# esquema_vortex_001.net
KiCad netlist of a schematic drawn in EAGLE
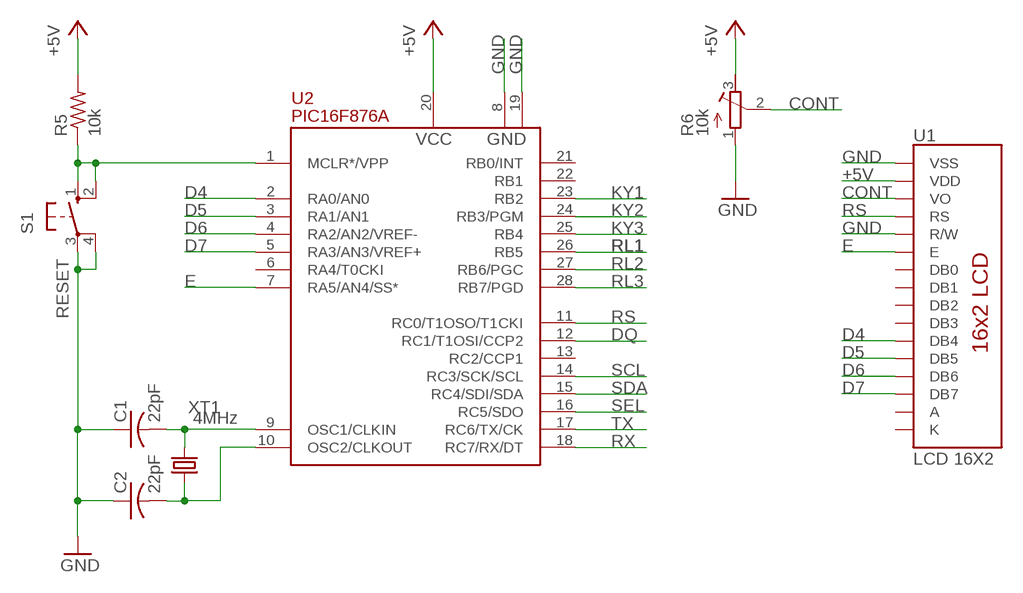
[diagram p0: schematic, sheet 1]
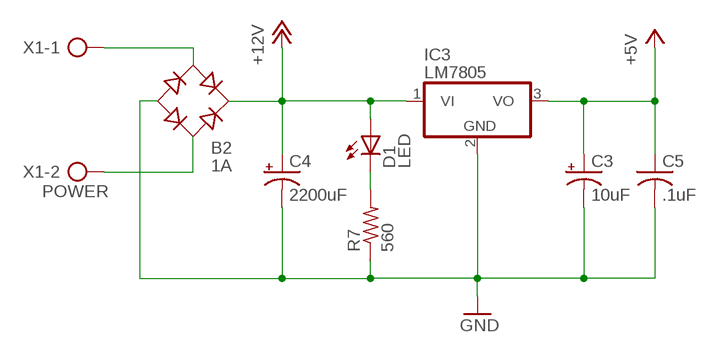
[diagram p1: schematic, sheet 2]
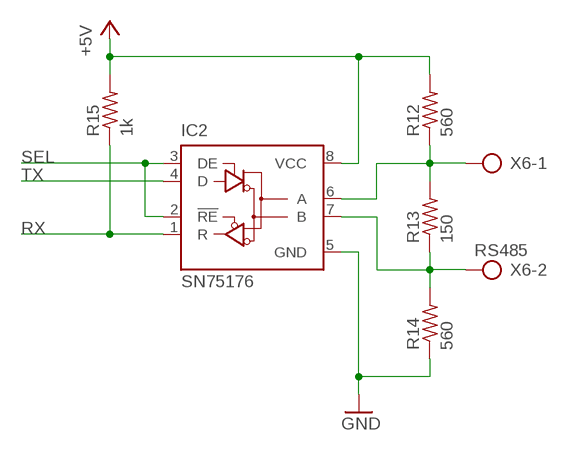
[diagram p2: schematic, sheet 3]
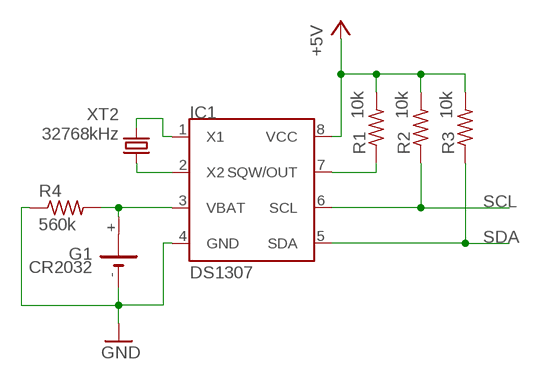
[diagram p3: schematic, sheet 4]
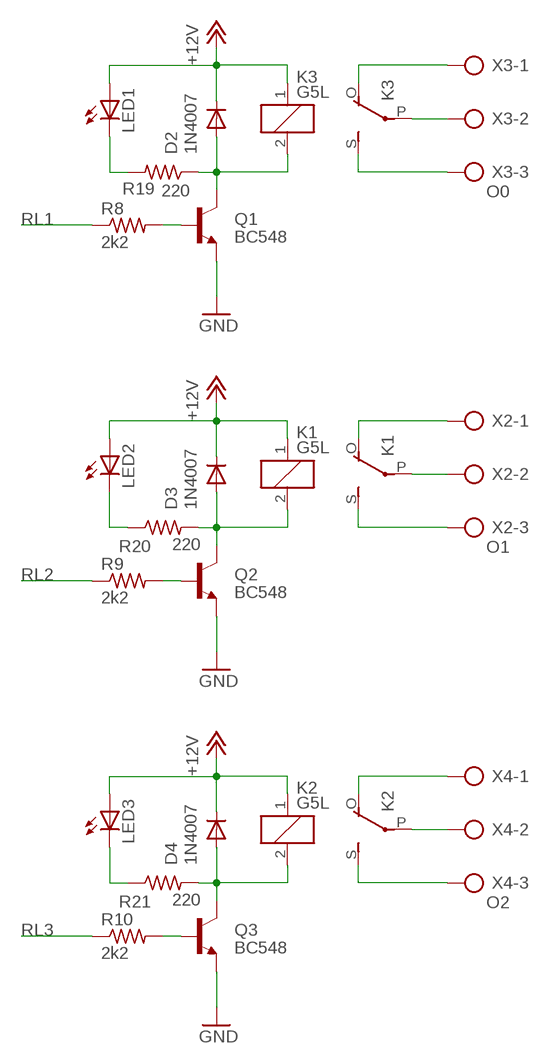
[diagram p4: schematic, sheet 5]
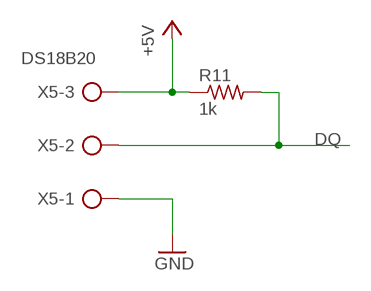
[diagram p5: schematic, sheet 6]
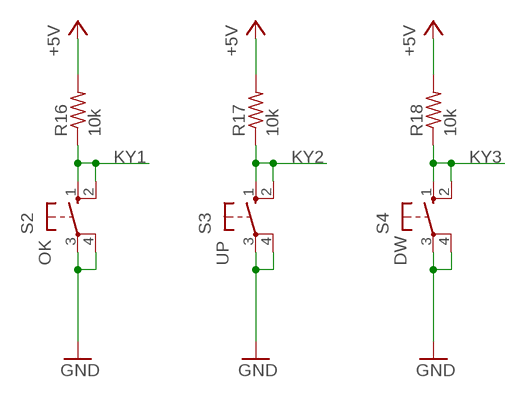
[diagram p6: schematic, sheet 7]

(export (version "E")
  (design (tool "Eeschema 10.0.6"))
  (components
    (comp (ref "IC2")
      (value "SN75176")
      (footprint "eagle-import:DIL08")
      (libsource (lib "eagle-import") (part "75176AP"))
    )
    (comp (ref "R12")
      (value "560")
      (footprint "eagle-import:0204_7")
      (libsource (lib "eagle-import") (part "R-US_0204/7"))
    )
    (comp (ref "R13")
      (value "150")
      (footprint "eagle-import:0204_7")
      (libsource (lib "eagle-import") (part "R-US_0204/7"))
    )
    (comp (ref "R14")
      (value "560")
      (footprint "eagle-import:0204_7")
      (libsource (lib "eagle-import") (part "R-US_0204/7"))
    )
    (comp (ref "R15")
      (value "1k")
      (footprint "eagle-import:0204_7")
      (libsource (lib "eagle-import") (part "R-US_0204/7"))
    )
    (comp (ref "X6")
      (value "RS485")
      (footprint "eagle-import:AK500_2-H")
      (libsource (lib "eagle-import") (part "AK500/2-H"))
    )
    (comp (ref "C1")
      (value "22pF")
      (footprint "eagle-import:C025-030X050")
      (libsource (lib "eagle-import") (part "C-US025-030X050"))
    )
    (comp (ref "C2")
      (value "22pF")
      (footprint "eagle-import:C025-030X050")
      (libsource (lib "eagle-import") (part "C-US025-030X050"))
    )
    (comp (ref "R5")
      (value "10k")
      (footprint "eagle-import:0204_7")
      (libsource (lib "eagle-import") (part "rcl_R-US_0204/7"))
    )
    (comp (ref "R6")
      (value "10k")
      (footprint "eagle-import:RTRIM3296W")
      (libsource (lib "eagle-import") (part "R-TRIMM3296W"))
    )
    (comp (ref "S1")
      (value "RESET")
      (footprint "eagle-import:B3F-10XX")
      (fields (field (name "MPN") "B3F-1000"))
      (libsource (lib "eagle-import") (part "10-XX"))
    )
    (comp (ref "U1")
      (value "LCD 16X2")
      (footprint "eagle-import:LCD-16X2")
      (libsource (lib "eagle-import") (part "LCD-16X2SILK"))
    )
    (comp (ref "U2")
      (value "PIC16F876A")
      (footprint "eagle-import:DIL28-3")
      (libsource (lib "eagle-import") (part "16F876SP"))
    )
    (comp (ref "XT1")
      (value "4MHz")
      (footprint "eagle-import:HC49_S")
      (libsource (lib "eagle-import") (part "CRYSTALHC49S"))
    )
    (comp (ref "D2")
      (value "1N4007")
      (footprint "eagle-import:DO41-10")
      (libsource (lib "eagle-import") (part "1N4004"))
    )
    (comp (ref "D3")
      (value "1N4007")
      (footprint "eagle-import:DO41-10")
      (libsource (lib "eagle-import") (part "1N4004"))
    )
    (comp (ref "D4")
      (value "1N4007")
      (footprint "eagle-import:DO41-10")
      (libsource (lib "eagle-import") (part "1N4004"))
    )
    (comp (ref "K1")
      (value "G5L")
      (footprint "eagle-import:G5LE")
      (libsource (lib "eagle-import") (part "G5L"))
    )
    (comp (ref "K2")
      (value "G5L")
      (footprint "eagle-import:G5LE")
      (libsource (lib "eagle-import") (part "G5L"))
    )
    (comp (ref "K3")
      (value "G5L")
      (footprint "eagle-import:G5LE")
      (libsource (lib "eagle-import") (part "G5L"))
    )
    (comp (ref "LED1")
      (value "LED")
      (footprint "eagle-import:LED3MM")
      (libsource (lib "eagle-import") (part "led_LED3MM"))
    )
    (comp (ref "LED2")
      (value "LED")
      (footprint "eagle-import:LED3MM")
      (libsource (lib "eagle-import") (part "led_LED3MM"))
    )
    (comp (ref "LED3")
      (value "LED")
      (footprint "eagle-import:LED3MM")
      (libsource (lib "eagle-import") (part "led_LED3MM"))
    )
    (comp (ref "Q1")
      (value "BC548")
      (footprint "eagle-import:TO92-EBC")
      (libsource (lib "eagle-import") (part "BC548"))
    )
    (comp (ref "Q2")
      (value "BC548")
      (footprint "eagle-import:TO92-EBC")
      (libsource (lib "eagle-import") (part "BC548"))
    )
    (comp (ref "Q3")
      (value "BC548")
      (footprint "eagle-import:TO92-EBC")
      (libsource (lib "eagle-import") (part "BC548"))
    )
    (comp (ref "R8")
      (value "2k2")
      (footprint "eagle-import:0204_7")
      (libsource (lib "eagle-import") (part "R-US_0204/7"))
    )
    (comp (ref "R9")
      (value "2k2")
      (footprint "eagle-import:0204_7")
      (libsource (lib "eagle-import") (part "R-US_0204/7"))
    )
    (comp (ref "R10")
      (value "2k2")
      (footprint "eagle-import:0204_7")
      (libsource (lib "eagle-import") (part "R-US_0204/7"))
    )
    (comp (ref "R19")
      (value "220")
      (footprint "eagle-import:0204_7")
      (libsource (lib "eagle-import") (part "R-US_0204/7"))
    )
    (comp (ref "R20")
      (value "220")
      (footprint "eagle-import:0204_7")
      (libsource (lib "eagle-import") (part "R-US_0204/7"))
    )
    (comp (ref "R21")
      (value "220")
      (footprint "eagle-import:0204_7")
      (libsource (lib "eagle-import") (part "R-US_0204/7"))
    )
    (comp (ref "X2")
      (value "O1")
      (footprint "eagle-import:AK500_3")
      (libsource (lib "eagle-import") (part "AK500/3"))
    )
    (comp (ref "X3")
      (value "O0")
      (footprint "eagle-import:AK500_3")
      (libsource (lib "eagle-import") (part "AK500/3"))
    )
    (comp (ref "X4")
      (value "O2")
      (footprint "eagle-import:AK500_3")
      (libsource (lib "eagle-import") (part "AK500/3"))
    )
    (comp (ref "G1")
      (value "CR2032")
      (footprint "eagle-import:CR2032H")
      (libsource (lib "eagle-import") (part "CR2032H"))
    )
    (comp (ref "IC1")
      (value "DS1307")
      (footprint "eagle-import:DIL08")
      (libsource (lib "eagle-import") (part "DS1307PDIP"))
    )
    (comp (ref "R1")
      (value "10k")
      (footprint "eagle-import:0204_7")
      (libsource (lib "eagle-import") (part "R-US_0204/7"))
    )
    (comp (ref "R2")
      (value "10k")
      (footprint "eagle-import:0204_7")
      (libsource (lib "eagle-import") (part "R-US_0204/7"))
    )
    (comp (ref "R3")
      (value "10k")
      (footprint "eagle-import:0204_7")
      (libsource (lib "eagle-import") (part "R-US_0204/7"))
    )
    (comp (ref "R4")
      (value "560k")
      (footprint "eagle-import:0204_7")
      (libsource (lib "eagle-import") (part "R-US_0204/7"))
    )
    (comp (ref "XT2")
      (value "32768kHz")
      (footprint "eagle-import:HC49_S")
      (libsource (lib "eagle-import") (part "CRYSTALHC49S"))
    )
    (comp (ref "B2")
      (value "1A")
      (footprint "eagle-import:RB1A")
      (libsource (lib "eagle-import") (part "RB1A"))
    )
    (comp (ref "C3")
      (value "10uF")
      (footprint "eagle-import:E2,5-7")
      (libsource (lib "eagle-import") (part "CPOL-USE2.5-7"))
    )
    (comp (ref "C4")
      (value "2200uF")
      (footprint "eagle-import:E3,5-10")
      (libsource (lib "eagle-import") (part "CPOL-USE3.5-10"))
    )
    (comp (ref "C5")
      (value ".1uF")
      (footprint "eagle-import:C050-024X044")
      (libsource (lib "eagle-import") (part "C-US050-024X044"))
    )
    (comp (ref "D1")
      (value "LED")
      (footprint "eagle-import:LED3MM")
      (libsource (lib "eagle-import") (part "LED3MM"))
    )
    (comp (ref "IC3")
      (value "LM7805")
      (footprint "eagle-import:TO220V")
      (libsource (lib "eagle-import") (part "78TV12"))
    )
    (comp (ref "R7")
      (value "560")
      (footprint "eagle-import:0204_7")
      (libsource (lib "eagle-import") (part "rcl_R-US_0204/7"))
    )
    (comp (ref "X1")
      (value "POWER")
      (footprint "eagle-import:AK500_2")
      (libsource (lib "eagle-import") (part "AK500/2"))
    )
    (comp (ref "R11")
      (value "1k")
      (footprint "eagle-import:0204_7")
      (libsource (lib "eagle-import") (part "R-US_0204/7"))
    )
    (comp (ref "X5")
      (value "DS18B20")
      (footprint "eagle-import:AK500_3-H")
      (libsource (lib "eagle-import") (part "AK500/3-H"))
    )
    (comp (ref "R16")
      (value "10k")
      (footprint "eagle-import:0204_7")
      (libsource (lib "eagle-import") (part "rcl_R-US_0204/7"))
    )
    (comp (ref "R17")
      (value "10k")
      (footprint "eagle-import:0204_7")
      (libsource (lib "eagle-import") (part "rcl_R-US_0204/7"))
    )
    (comp (ref "R18")
      (value "10k")
      (footprint "eagle-import:0204_7")
      (libsource (lib "eagle-import") (part "rcl_R-US_0204/7"))
    )
    (comp (ref "S2")
      (value "OK")
      (footprint "eagle-import:B3F-10XX")
      (fields (field (name "MPN") "B3F-1000"))
      (libsource (lib "eagle-import") (part "10-XX"))
    )
    (comp (ref "S3")
      (value "UP")
      (footprint "eagle-import:B3F-10XX")
      (fields (field (name "MPN") "B3F-1000"))
      (libsource (lib "eagle-import") (part "10-XX"))
    )
    (comp (ref "S4")
      (value "DW")
      (footprint "eagle-import:B3F-10XX")
      (fields (field (name "MPN") "B3F-1000"))
      (libsource (lib "eagle-import") (part "10-XX"))
    )
  )
  (nets
    (net (code "1") (name "+5V") (class "Default")
      (node (ref "C3") (pin "+") (pinfunction "+_+") (pintype "passive"))
      (node (ref "C5") (pin "1") (pinfunction "1_1") (pintype "passive"))
      (node (ref "IC1") (pin "8") (pinfunction "VCC_8") (pintype "power_in"))
      (node (ref "IC2") (pin "8") (pinfunction "VCC_8") (pintype "power_in"))
      (node (ref "IC3") (pin "3") (pinfunction "VO_3") (pintype "passive"))
      (node (ref "R1") (pin "2") (pinfunction "2_2") (pintype "passive"))
      (node (ref "R11") (pin "1") (pinfunction "1_1") (pintype "passive"))
      (node (ref "R12") (pin "2") (pinfunction "2_2") (pintype "passive"))
      (node (ref "R15") (pin "2") (pinfunction "2_2") (pintype "passive"))
      (node (ref "R16") (pin "2") (pinfunction "2_2") (pintype "passive"))
      (node (ref "R17") (pin "2") (pinfunction "2_2") (pintype "passive"))
      (node (ref "R18") (pin "2") (pinfunction "2_2") (pintype "passive"))
      (node (ref "R2") (pin "2") (pinfunction "2_2") (pintype "passive"))
      (node (ref "R3") (pin "2") (pinfunction "2_2") (pintype "passive"))
      (node (ref "R5") (pin "2") (pinfunction "2_2") (pintype "passive"))
      (node (ref "R6") (pin "3") (pinfunction "E_3") (pintype "passive"))
      (node (ref "U1") (pin "2") (pinfunction "VDD_2") (pintype "power_in"))
      (node (ref "U2") (pin "20") (pinfunction "VCC_20") (pintype "power_in"))
      (node (ref "X5") (pin "3") (pinfunction "KL_3") (pintype "passive"))
    )
    (net (code "2") (name "+12V") (class "Default")
      (node (ref "B2") (pin "+") (pinfunction "+_+") (pintype "passive"))
      (node (ref "C4") (pin "+") (pinfunction "+_+") (pintype "passive"))
      (node (ref "D1") (pin "A") (pinfunction "A_A") (pintype "passive"))
      (node (ref "D2") (pin "C") (pinfunction "C_C") (pintype "passive"))
      (node (ref "D3") (pin "C") (pinfunction "C_C") (pintype "passive"))
      (node (ref "D4") (pin "C") (pinfunction "C_C") (pintype "passive"))
      (node (ref "IC3") (pin "1") (pinfunction "VI_1") (pintype "input"))
      (node (ref "K1") (pin "1") (pinfunction "1_1") (pintype "passive"))
      (node (ref "K2") (pin "1") (pinfunction "1_1") (pintype "passive"))
      (node (ref "K3") (pin "1") (pinfunction "1_1") (pintype "passive"))
      (node (ref "LED1") (pin "A") (pinfunction "A_A") (pintype "passive"))
      (node (ref "LED2") (pin "A") (pinfunction "A_A") (pintype "passive"))
      (node (ref "LED3") (pin "A") (pinfunction "A_A") (pintype "passive"))
    )
    (net (code "3") (name "A") (class "Default")
      (node (ref "U1") (pin "15") (pinfunction "A_15") (pintype "power_in"))
    )
    (net (code "4") (name "CONT") (class "Default")
      (node (ref "R6") (pin "2") (pinfunction "S_2") (pintype "passive"))
      (node (ref "U1") (pin "3") (pinfunction "VO_3") (pintype "bidirectional"))
    )
    (net (code "5") (name "D4") (class "Default")
      (node (ref "U1") (pin "11") (pinfunction "DB4_11") (pintype "bidirectional"))
      (node (ref "U2") (pin "2") (pinfunction "RA0/AN0_2") (pintype "bidirectional"))
    )
    (net (code "6") (name "D5") (class "Default")
      (node (ref "U1") (pin "12") (pinfunction "DB5_12") (pintype "bidirectional"))
      (node (ref "U2") (pin "3") (pinfunction "RA1/AN1_3") (pintype "bidirectional"))
    )
    (net (code "7") (name "D6") (class "Default")
      (node (ref "U1") (pin "13") (pinfunction "DB6_13") (pintype "bidirectional"))
      (node (ref "U2") (pin "4") (pinfunction "RA2/AN2/VREF-_4") (pintype "bidirectional"))
    )
    (net (code "8") (name "D7") (class "Default")
      (node (ref "U1") (pin "14") (pinfunction "DB7_14") (pintype "bidirectional"))
      (node (ref "U2") (pin "5") (pinfunction "RA3/AN3/VREF+_5") (pintype "bidirectional"))
    )
    (net (code "9") (name "DQ") (class "Default")
      (node (ref "R11") (pin "2") (pinfunction "2_2") (pintype "passive"))
      (node (ref "U2") (pin "12") (pinfunction "RC1/T1OSI/CCP2_12") (pintype "bidirectional"))
      (node (ref "X5") (pin "2") (pinfunction "KL_2") (pintype "passive"))
    )
    (net (code "10") (name "E") (class "Default")
      (node (ref "U1") (pin "6") (pinfunction "E_6") (pintype "input"))
      (node (ref "U2") (pin "7") (pinfunction "RA5/AN4/SS*_7") (pintype "bidirectional"))
    )
    (net (code "11") (name "GND") (class "Default")
      (node (ref "B2") (pin "-") (pinfunction "-_-") (pintype "passive"))
      (node (ref "C1") (pin "1") (pinfunction "1_1") (pintype "passive"))
      (node (ref "C2") (pin "1") (pinfunction "1_1") (pintype "passive"))
      (node (ref "C3") (pin "-") (pinfunction "-_-") (pintype "passive"))
      (node (ref "C4") (pin "-") (pinfunction "-_-") (pintype "passive"))
      (node (ref "C5") (pin "2") (pinfunction "2_2") (pintype "passive"))
      (node (ref "G1") (pin "-") (pinfunction "-_-") (pintype "passive"))
      (node (ref "IC1") (pin "4") (pinfunction "GND_4") (pintype "power_in"))
      (node (ref "IC2") (pin "5") (pinfunction "GND_5") (pintype "power_in"))
      (node (ref "IC3") (pin "2") (pinfunction "GND_2") (pintype "passive"))
      (node (ref "Q1") (pin "E") (pinfunction "E_E") (pintype "passive"))
      (node (ref "Q2") (pin "E") (pinfunction "E_E") (pintype "passive"))
      (node (ref "Q3") (pin "E") (pinfunction "E_E") (pintype "passive"))
      (node (ref "R14") (pin "1") (pinfunction "1_1") (pintype "passive"))
      (node (ref "R4") (pin "1") (pinfunction "1_1") (pintype "passive"))
      (node (ref "R6") (pin "1") (pinfunction "A_1") (pintype "passive"))
      (node (ref "R7") (pin "1") (pinfunction "1_1") (pintype "passive"))
      (node (ref "S1") (pin "3") (pinfunction "P_3") (pintype "passive"))
      (node (ref "S1") (pin "4") (pinfunction "P1_4") (pintype "passive"))
      (node (ref "S2") (pin "3") (pinfunction "P_3") (pintype "passive"))
      (node (ref "S2") (pin "4") (pinfunction "P1_4") (pintype "passive"))
      (node (ref "S3") (pin "3") (pinfunction "P_3") (pintype "passive"))
      (node (ref "S3") (pin "4") (pinfunction "P1_4") (pintype "passive"))
      (node (ref "S4") (pin "3") (pinfunction "P_3") (pintype "passive"))
      (node (ref "S4") (pin "4") (pinfunction "P1_4") (pintype "passive"))
      (node (ref "U1") (pin "1") (pinfunction "VSS_1") (pintype "power_in"))
      (node (ref "U1") (pin "5") (pinfunction "R/W_5") (pintype "input"))
      (node (ref "U2") (pin "19") (pinfunction "GND_19") (pintype "power_in"))
      (node (ref "U2") (pin "8") (pinfunction "GND_8") (pintype "power_in"))
      (node (ref "X5") (pin "1") (pinfunction "KL_1") (pintype "passive"))
    )
    (net (code "12") (name "K") (class "Default")
      (node (ref "U1") (pin "16") (pinfunction "K_16") (pintype "power_in"))
    )
    (net (code "13") (name "KY1") (class "Default")
      (node (ref "R16") (pin "1") (pinfunction "1_1") (pintype "passive"))
      (node (ref "S2") (pin "1") (pinfunction "S_1") (pintype "passive"))
      (node (ref "S2") (pin "2") (pinfunction "S1_2") (pintype "passive"))
      (node (ref "U2") (pin "23") (pinfunction "RB2_23") (pintype "bidirectional"))
    )
    (net (code "14") (name "KY2") (class "Default")
      (node (ref "R17") (pin "1") (pinfunction "1_1") (pintype "passive"))
      (node (ref "S3") (pin "1") (pinfunction "S_1") (pintype "passive"))
      (node (ref "S3") (pin "2") (pinfunction "S1_2") (pintype "passive"))
      (node (ref "U2") (pin "24") (pinfunction "RB3/PGM_24") (pintype "bidirectional"))
    )
    (net (code "15") (name "KY3") (class "Default")
      (node (ref "R18") (pin "1") (pinfunction "1_1") (pintype "passive"))
      (node (ref "S4") (pin "1") (pinfunction "S_1") (pintype "passive"))
      (node (ref "S4") (pin "2") (pinfunction "S1_2") (pintype "passive"))
      (node (ref "U2") (pin "25") (pinfunction "RB4_25") (pintype "bidirectional"))
    )
    (net (code "16") (name "Net-(D1-C)") (class "Default")
      (node (ref "D1") (pin "K") (pinfunction "C_K") (pintype "passive"))
      (node (ref "R7") (pin "2") (pinfunction "2_2") (pintype "passive"))
    )
    (net (code "17") (name "Net-(D2-PadA)") (class "Default")
      (node (ref "D2") (pin "A") (pinfunction "A_A") (pintype "passive"))
      (node (ref "K3") (pin "2") (pinfunction "2_2") (pintype "passive"))
      (node (ref "Q1") (pin "C") (pinfunction "C_C") (pintype "passive"))
      (node (ref "R19") (pin "1") (pinfunction "1_1") (pintype "passive"))
    )
    (net (code "18") (name "Net-(D3-PadA)") (class "Default")
      (node (ref "D3") (pin "A") (pinfunction "A_A") (pintype "passive"))
      (node (ref "K1") (pin "2") (pinfunction "2_2") (pintype "passive"))
      (node (ref "Q2") (pin "C") (pinfunction "C_C") (pintype "passive"))
      (node (ref "R20") (pin "2") (pinfunction "2_2") (pintype "passive"))
    )
    (net (code "19") (name "Net-(D4-PadA)") (class "Default")
      (node (ref "D4") (pin "A") (pinfunction "A_A") (pintype "passive"))
      (node (ref "K2") (pin "2") (pinfunction "2_2") (pintype "passive"))
      (node (ref "Q3") (pin "C") (pinfunction "C_C") (pintype "passive"))
      (node (ref "R21") (pin "2") (pinfunction "2_2") (pintype "passive"))
    )
    (net (code "20") (name "Net-(IC1-SQW{slash}OUT)") (class "Default")
      (node (ref "IC1") (pin "7") (pinfunction "SQW/OUT_7") (pintype "output"))
      (node (ref "R1") (pin "1") (pinfunction "1_1") (pintype "passive"))
    )
    (net (code "21") (name "Net-(IC1-VBAT)") (class "Default")
      (node (ref "G1") (pin "+") (pinfunction "+_+") (pintype "passive"))
      (node (ref "IC1") (pin "3") (pinfunction "VBAT_3") (pintype "power_in"))
      (node (ref "R4") (pin "2") (pinfunction "2_2") (pintype "passive"))
    )
    (net (code "22") (name "Net-(IC1-X1)") (class "Default")
      (node (ref "IC1") (pin "1") (pinfunction "X1_1") (pintype "input"))
      (node (ref "XT2") (pin "2") (pinfunction "2_2") (pintype "passive"))
    )
    (net (code "23") (name "Net-(IC1-X2)") (class "Default")
      (node (ref "IC1") (pin "2") (pinfunction "X2_2") (pintype "output"))
      (node (ref "XT2") (pin "1") (pinfunction "1_1") (pintype "passive"))
    )
    (net (code "24") (name "Net-(IC2-A)") (class "Default")
      (node (ref "IC2") (pin "6") (pinfunction "A_6") (pintype "output"))
      (node (ref "R12") (pin "1") (pinfunction "1_1") (pintype "passive"))
      (node (ref "R13") (pin "2") (pinfunction "2_2") (pintype "passive"))
      (node (ref "X6") (pin "1") (pinfunction "KL_1") (pintype "passive"))
    )
    (net (code "25") (name "Net-(IC2-B)") (class "Default")
      (node (ref "IC2") (pin "7") (pinfunction "B_7") (pintype "output"))
      (node (ref "R13") (pin "1") (pinfunction "1_1") (pintype "passive"))
      (node (ref "R14") (pin "2") (pinfunction "2_2") (pintype "passive"))
      (node (ref "X6") (pin "2") (pinfunction "KL_2") (pintype "passive"))
    )
    (net (code "26") (name "Net-(LED1-C)") (class "Default")
      (node (ref "LED1") (pin "K") (pinfunction "C_K") (pintype "passive"))
      (node (ref "R19") (pin "2") (pinfunction "2_2") (pintype "passive"))
    )
    (net (code "27") (name "Net-(LED2-C)") (class "Default")
      (node (ref "LED2") (pin "K") (pinfunction "C_K") (pintype "passive"))
      (node (ref "R20") (pin "1") (pinfunction "1_1") (pintype "passive"))
    )
    (net (code "28") (name "Net-(LED3-C)") (class "Default")
      (node (ref "LED3") (pin "K") (pinfunction "C_K") (pintype "passive"))
      (node (ref "R21") (pin "1") (pinfunction "1_1") (pintype "passive"))
    )
    (net (code "29") (name "Net-(Q1-PadB)") (class "Default")
      (node (ref "Q1") (pin "B") (pinfunction "B_B") (pintype "passive"))
      (node (ref "R8") (pin "2") (pinfunction "2_2") (pintype "passive"))
    )
    (net (code "30") (name "Net-(Q2-PadB)") (class "Default")
      (node (ref "Q2") (pin "B") (pinfunction "B_B") (pintype "passive"))
      (node (ref "R9") (pin "2") (pinfunction "2_2") (pintype "passive"))
    )
    (net (code "31") (name "Net-(Q3-PadB)") (class "Default")
      (node (ref "Q3") (pin "B") (pinfunction "B_B") (pintype "passive"))
      (node (ref "R10") (pin "2") (pinfunction "2_2") (pintype "passive"))
    )
    (net (code "32") (name "Net-(S1-S)") (class "Default")
      (node (ref "R5") (pin "1") (pinfunction "1_1") (pintype "passive"))
      (node (ref "S1") (pin "1") (pinfunction "S_1") (pintype "passive"))
      (node (ref "S1") (pin "2") (pinfunction "S1_2") (pintype "passive"))
      (node (ref "U2") (pin "1") (pinfunction "MCLR*/VPP_1") (pintype "bidirectional"))
    )
    (net (code "33") (name "Net-(U2-OSC1{slash}CLKIN)") (class "Default")
      (node (ref "C1") (pin "2") (pinfunction "2_2") (pintype "passive"))
      (node (ref "U2") (pin "9") (pinfunction "OSC1/CLKIN_9") (pintype "bidirectional"))
      (node (ref "XT1") (pin "2") (pinfunction "2_2") (pintype "passive"))
    )
    (net (code "34") (name "Net-(U2-OSC2{slash}CLKOUT)") (class "Default")
      (node (ref "C2") (pin "2") (pinfunction "2_2") (pintype "passive"))
      (node (ref "U2") (pin "10") (pinfunction "OSC2/CLKOUT_10") (pintype "bidirectional"))
      (node (ref "XT1") (pin "1") (pinfunction "1_1") (pintype "passive"))
    )
    (net (code "35") (name "Net-(X1A-KL)") (class "Default")
      (node (ref "B2") (pin "AC1") (pinfunction "AC1_AC1") (pintype "passive"))
      (node (ref "X1") (pin "1") (pinfunction "KL_1") (pintype "passive"))
    )
    (net (code "36") (name "Net-(X1B-KL)") (class "Default")
      (node (ref "B2") (pin "AC2") (pinfunction "AC2_AC2") (pintype "passive"))
      (node (ref "X1") (pin "2") (pinfunction "KL_2") (pintype "passive"))
    )
    (net (code "37") (name "Net-(X2A-KL)") (class "Default")
      (node (ref "K1") (pin "O") (pinfunction "O_O") (pintype "passive"))
      (node (ref "X2") (pin "1") (pinfunction "KL_1") (pintype "passive"))
    )
    (net (code "38") (name "Net-(X2B-KL)") (class "Default")
      (node (ref "K1") (pin "P") (pinfunction "P_P") (pintype "passive"))
      (node (ref "X2") (pin "2") (pinfunction "KL_2") (pintype "passive"))
    )
    (net (code "39") (name "Net-(X2C-KL)") (class "Default")
      (node (ref "K1") (pin "S") (pinfunction "S_S") (pintype "passive"))
      (node (ref "X2") (pin "3") (pinfunction "KL_3") (pintype "passive"))
    )
    (net (code "40") (name "Net-(X3A-KL)") (class "Default")
      (node (ref "K3") (pin "O") (pinfunction "O_O") (pintype "passive"))
      (node (ref "X3") (pin "1") (pinfunction "KL_1") (pintype "passive"))
    )
    (net (code "41") (name "Net-(X3B-KL)") (class "Default")
      (node (ref "K3") (pin "P") (pinfunction "P_P") (pintype "passive"))
      (node (ref "X3") (pin "2") (pinfunction "KL_2") (pintype "passive"))
    )
    (net (code "42") (name "Net-(X3C-KL)") (class "Default")
      (node (ref "K3") (pin "S") (pinfunction "S_S") (pintype "passive"))
      (node (ref "X3") (pin "3") (pinfunction "KL_3") (pintype "passive"))
    )
    (net (code "43") (name "Net-(X4A-KL)") (class "Default")
      (node (ref "K2") (pin "O") (pinfunction "O_O") (pintype "passive"))
      (node (ref "X4") (pin "1") (pinfunction "KL_1") (pintype "passive"))
    )
    (net (code "44") (name "Net-(X4B-KL)") (class "Default")
      (node (ref "K2") (pin "P") (pinfunction "P_P") (pintype "passive"))
      (node (ref "X4") (pin "2") (pinfunction "KL_2") (pintype "passive"))
    )
    (net (code "45") (name "Net-(X4C-KL)") (class "Default")
      (node (ref "K2") (pin "S") (pinfunction "S_S") (pintype "passive"))
      (node (ref "X4") (pin "3") (pinfunction "KL_3") (pintype "passive"))
    )
    (net (code "46") (name "RL1") (class "Default")
      (node (ref "R8") (pin "1") (pinfunction "1_1") (pintype "passive"))
      (node (ref "U2") (pin "26") (pinfunction "RB5_26") (pintype "bidirectional"))
    )
    (net (code "47") (name "RL2") (class "Default")
      (node (ref "R9") (pin "1") (pinfunction "1_1") (pintype "passive"))
      (node (ref "U2") (pin "27") (pinfunction "RB6/PGC_27") (pintype "bidirectional"))
    )
    (net (code "48") (name "RL3") (class "Default")
      (node (ref "R10") (pin "1") (pinfunction "1_1") (pintype "passive"))
      (node (ref "U2") (pin "28") (pinfunction "RB7/PGD_28") (pintype "bidirectional"))
    )
    (net (code "49") (name "RS") (class "Default")
      (node (ref "U1") (pin "4") (pinfunction "RS_4") (pintype "input"))
      (node (ref "U2") (pin "11") (pinfunction "RC0/T1OSO/T1CKI_11") (pintype "bidirectional"))
    )
    (net (code "50") (name "RX") (class "Default")
      (node (ref "IC2") (pin "1") (pinfunction "R_1") (pintype "input"))
      (node (ref "R15") (pin "1") (pinfunction "1_1") (pintype "passive"))
      (node (ref "U2") (pin "18") (pinfunction "RC7/RX/DT_18") (pintype "bidirectional"))
    )
    (net (code "51") (name "SCL") (class "Default")
      (node (ref "IC1") (pin "6") (pinfunction "SCL_6") (pintype "input"))
      (node (ref "R2") (pin "1") (pinfunction "1_1") (pintype "passive"))
      (node (ref "U2") (pin "14") (pinfunction "RC3/SCK/SCL_14") (pintype "bidirectional"))
    )
    (net (code "52") (name "SDA") (class "Default")
      (node (ref "IC1") (pin "5") (pinfunction "SDA_5") (pintype "bidirectional"))
      (node (ref "R3") (pin "1") (pinfunction "1_1") (pintype "passive"))
      (node (ref "U2") (pin "15") (pinfunction "RC4/SDI/SDA_15") (pintype "bidirectional"))
    )
    (net (code "53") (name "SEL") (class "Default")
      (node (ref "IC2") (pin "2") (pinfunction "~{RE}_2") (pintype "input"))
      (node (ref "IC2") (pin "3") (pinfunction "DE_3") (pintype "input"))
      (node (ref "U2") (pin "16") (pinfunction "RC5/SDO_16") (pintype "bidirectional"))
    )
    (net (code "54") (name "TX") (class "Default")
      (node (ref "IC2") (pin "4") (pinfunction "D_4") (pintype "input"))
      (node (ref "U2") (pin "17") (pinfunction "RC6/TX/CK_17") (pintype "bidirectional"))
    )
    (net (code "55") (name "unconnected-(G1-+-Pad+@1)") (class "Default")
      (node (ref "G1") (pin "+@1") (pinfunction "+_+@1") (pintype "passive"))
    )
    (net (code "56") (name "unconnected-(U1-DB0-Pad7)") (class "Default")
      (node (ref "U1") (pin "7") (pinfunction "DB0_7") (pintype "bidirectional"))
    )
    (net (code "57") (name "unconnected-(U1-DB1-Pad8)") (class "Default")
      (node (ref "U1") (pin "8") (pinfunction "DB1_8") (pintype "bidirectional"))
    )
    (net (code "58") (name "unconnected-(U1-DB2-Pad9)") (class "Default")
      (node (ref "U1") (pin "9") (pinfunction "DB2_9") (pintype "bidirectional"))
    )
    (net (code "59") (name "unconnected-(U1-DB3-Pad10)") (class "Default")
      (node (ref "U1") (pin "10") (pinfunction "DB3_10") (pintype "bidirectional"))
    )
    (net (code "60") (name "unconnected-(U2-RA4{slash}T0CKI-Pad6)") (class "Default")
      (node (ref "U2") (pin "6") (pinfunction "RA4/T0CKI_6") (pintype "bidirectional"))
    )
    (net (code "61") (name "unconnected-(U2-RB0{slash}INT-Pad21)") (class "Default")
      (node (ref "U2") (pin "21") (pinfunction "RB0/INT_21") (pintype "bidirectional"))
    )
    (net (code "62") (name "unconnected-(U2-RB1-Pad22)") (class "Default")
      (node (ref "U2") (pin "22") (pinfunction "RB1_22") (pintype "bidirectional"))
    )
    (net (code "63") (name "unconnected-(U2-RC2{slash}CCP1-Pad13)") (class "Default")
      (node (ref "U2") (pin "13") (pinfunction "RC2/CCP1_13") (pintype "bidirectional"))
    )
  )
)
